# S7CAS-PLEIADES-CARTE-MERE_Pxx_DDR.net
KiCad netlist of a schematic drawn in Altium Designer
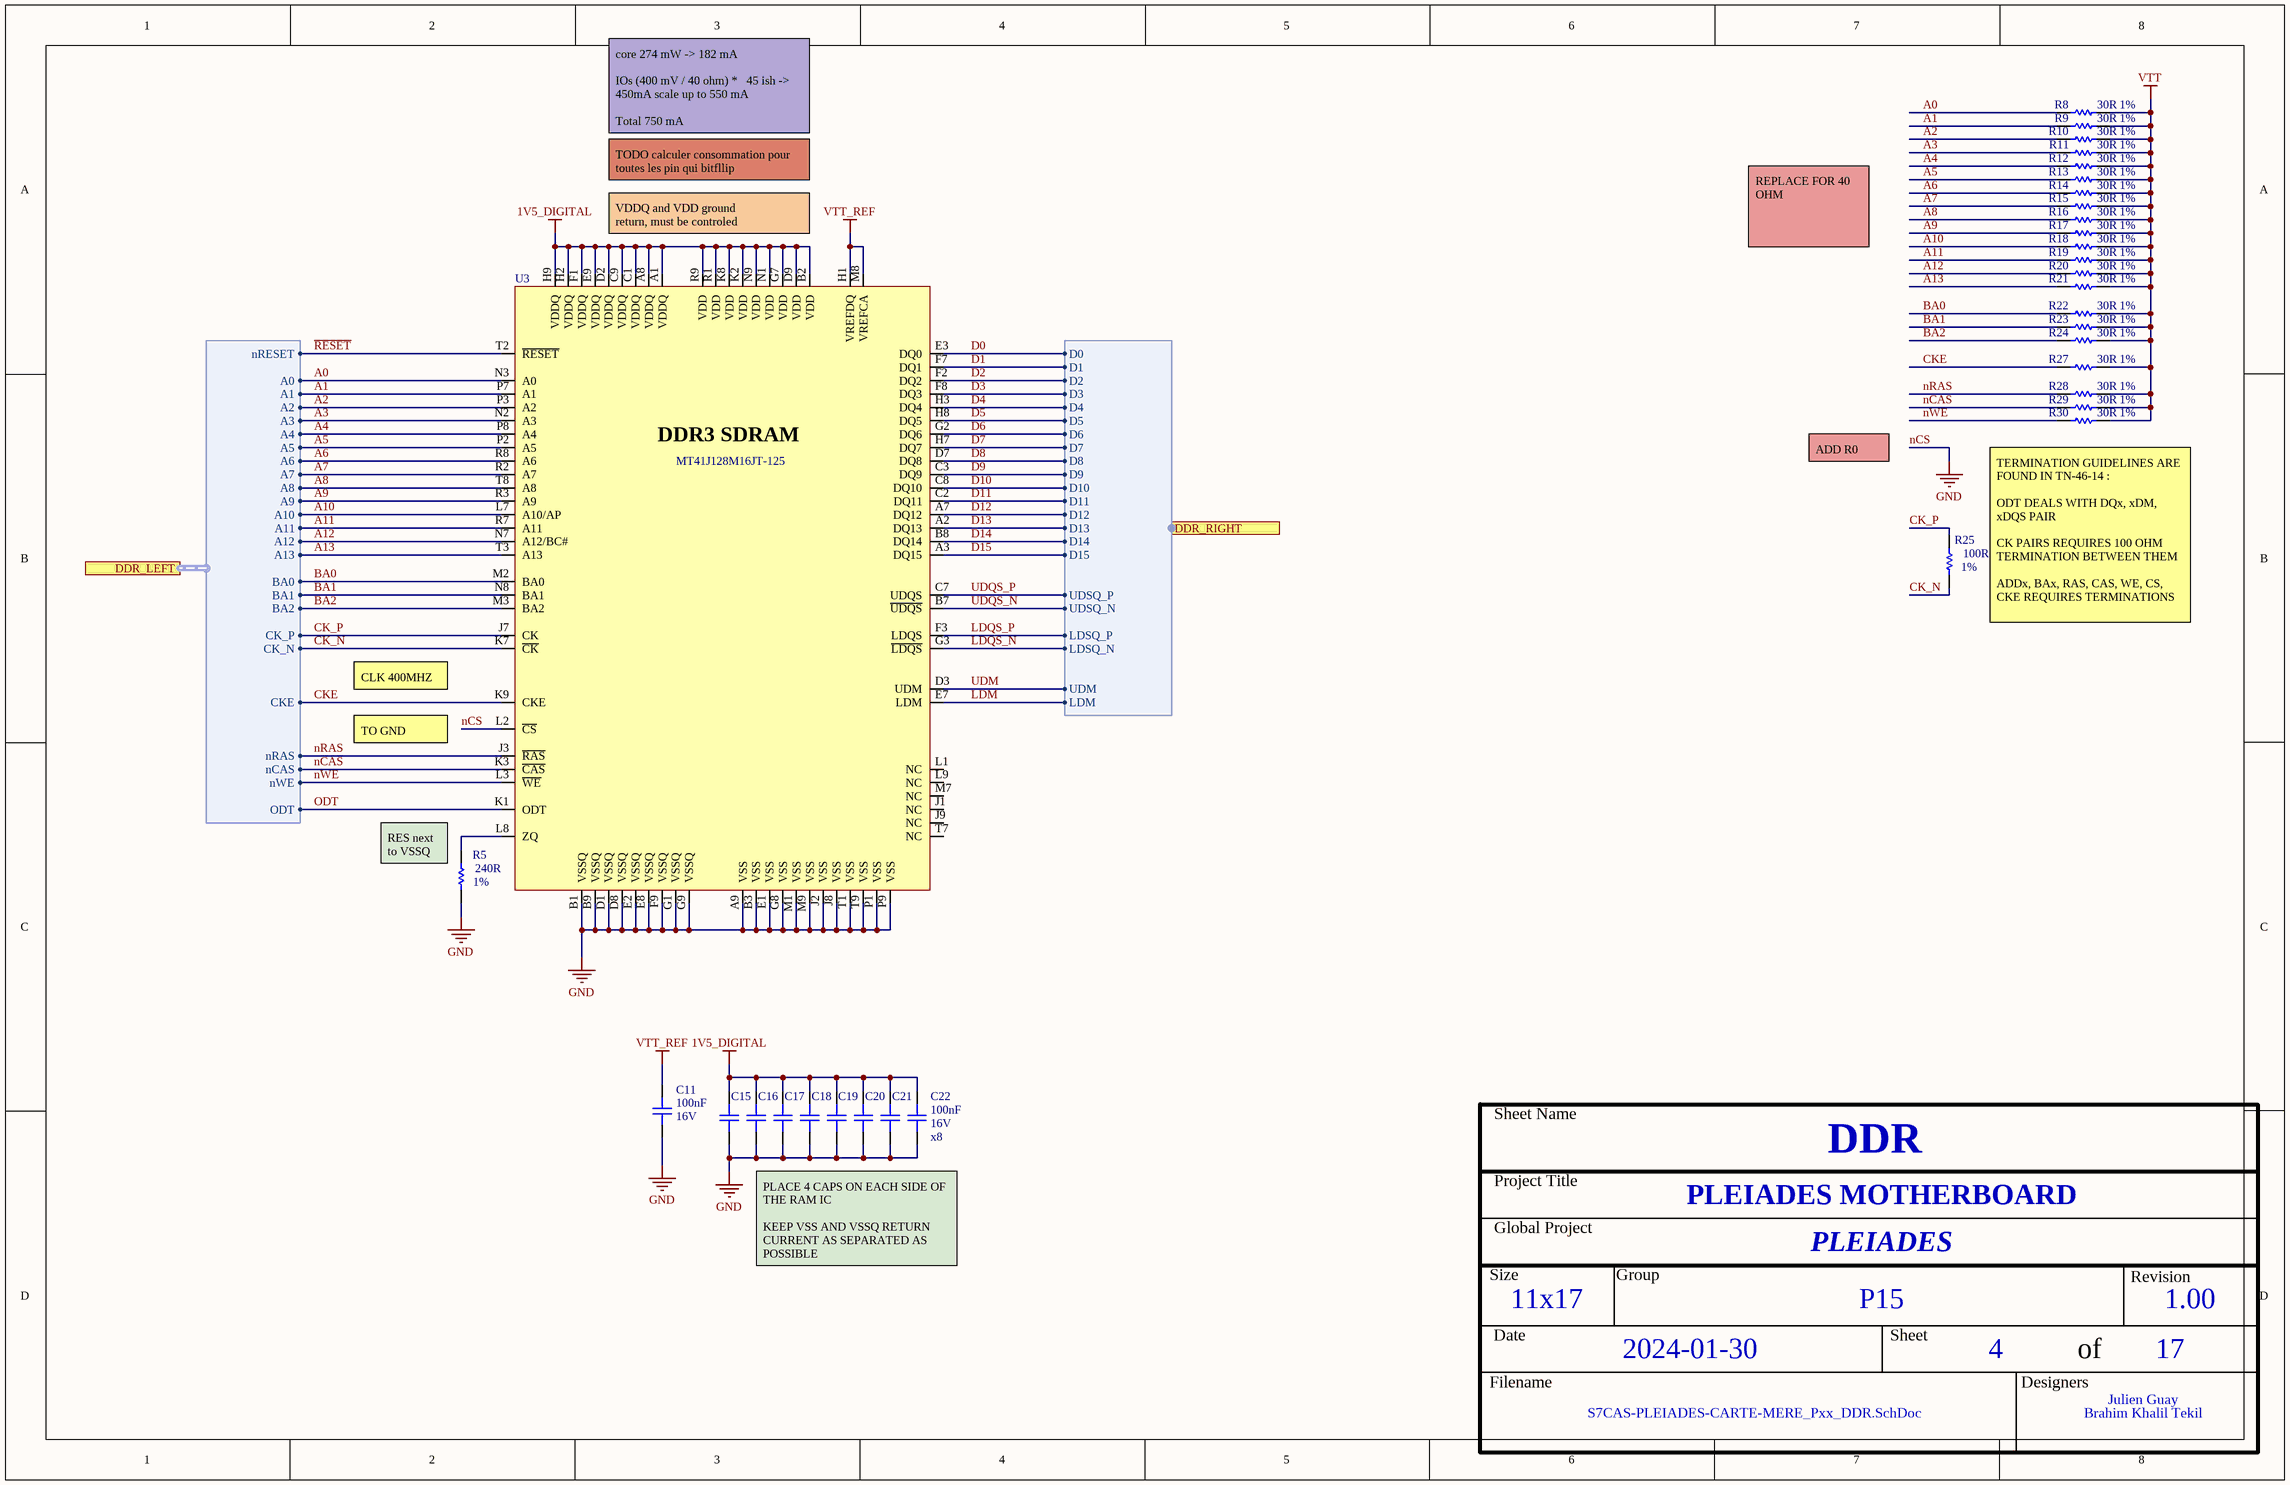
[diagram p0: S7CAS-PLEIADES-CARTE-MERE_Pxx_DDR.SchDoc]

(export (version "E")
  (design (tool "Eeschema 10.0.6"))
  (components
    (comp (ref "C11")
      (value "100nF")
      (footprint "CAP_0603")
      (description "CAP - 0603")
      (fields (field (name "VOLTAGE") "16V") (field (name "CREATEDBY") "Jonathan Bouchard"))
      (libsource (lib "S7CAS_LIB2023") (part "CAP - 0603"))
    )
    (comp (ref "C15")
      (value "CAP - 0603")
      (footprint "CAP_0603")
      (fields (field (name "VOLTAGE") "16V") (field (name "CREATEDBY") "Jonathan Bouchard"))
      (libsource (lib "S7CAS_LIB2023") (part "CAP - 0603"))
    )
    (comp (ref "C16")
      (value "CAP - 0603")
      (footprint "CAP_0603")
      (fields (field (name "VOLTAGE") "16V") (field (name "CREATEDBY") "Jonathan Bouchard"))
      (libsource (lib "S7CAS_LIB2023") (part "CAP - 0603"))
    )
    (comp (ref "C17")
      (value "CAP - 0603")
      (footprint "CAP_0603")
      (fields (field (name "VOLTAGE") "16V") (field (name "CREATEDBY") "Jonathan Bouchard"))
      (libsource (lib "S7CAS_LIB2023") (part "CAP - 0603"))
    )
    (comp (ref "C18")
      (value "CAP - 0603")
      (footprint "CAP_0603")
      (fields (field (name "VOLTAGE") "16V") (field (name "CREATEDBY") "Jonathan Bouchard"))
      (libsource (lib "S7CAS_LIB2023") (part "CAP - 0603"))
    )
    (comp (ref "C19")
      (value "CAP - 0603")
      (footprint "CAP_0603")
      (fields (field (name "VOLTAGE") "16V") (field (name "CREATEDBY") "Jonathan Bouchard"))
      (libsource (lib "S7CAS_LIB2023") (part "CAP - 0603"))
    )
    (comp (ref "C20")
      (value "CAP - 0603")
      (footprint "CAP_0603")
      (fields (field (name "VOLTAGE") "16V") (field (name "CREATEDBY") "Jonathan Bouchard"))
      (libsource (lib "S7CAS_LIB2023") (part "CAP - 0603"))
    )
    (comp (ref "C21")
      (value "CAP - 0603")
      (footprint "CAP_0603")
      (fields (field (name "VOLTAGE") "16V") (field (name "CREATEDBY") "Jonathan Bouchard"))
      (libsource (lib "S7CAS_LIB2023") (part "CAP - 0603"))
    )
    (comp (ref "C22")
      (value "100nF")
      (footprint "CAP_0603")
      (description "CAP - 0603")
      (fields (field (name "VOLTAGE") "16V") (field (name "CREATEDBY") "Jonathan Bouchard"))
      (libsource (lib "S7CAS_LIB2023") (part "CAP - 0603"))
    )
    (comp (ref "R5")
      (value "240R")
      (footprint "RES_0603")
      (description "RES - 0603")
      (fields (field (name "PRECISION") "1%") (field (name "CREATEDBY") "Jonathan Bouchard"))
      (libsource (lib "S7CAS_LIB2023") (part "RES - 0603"))
    )
    (comp (ref "R8")
      (value "30R")
      (footprint "RES_0603")
      (description "RES - 0603")
      (fields (field (name "PRECISION") "1%") (field (name "CREATEDBY") "Jonathan Bouchard"))
      (libsource (lib "S7CAS_LIB2023") (part "RES - 0603"))
    )
    (comp (ref "R9")
      (value "30R")
      (footprint "RES_0603")
      (description "RES - 0603")
      (fields (field (name "PRECISION") "1%") (field (name "CREATEDBY") "Jonathan Bouchard"))
      (libsource (lib "S7CAS_LIB2023") (part "RES - 0603"))
    )
    (comp (ref "R10")
      (value "30R")
      (footprint "RES_0603")
      (description "RES - 0603")
      (fields (field (name "PRECISION") "1%") (field (name "CREATEDBY") "Jonathan Bouchard"))
      (libsource (lib "S7CAS_LIB2023") (part "RES - 0603"))
    )
    (comp (ref "R11")
      (value "30R")
      (footprint "RES_0603")
      (description "RES - 0603")
      (fields (field (name "PRECISION") "1%") (field (name "CREATEDBY") "Jonathan Bouchard"))
      (libsource (lib "S7CAS_LIB2023") (part "RES - 0603"))
    )
    (comp (ref "R12")
      (value "30R")
      (footprint "RES_0603")
      (description "RES - 0603")
      (fields (field (name "PRECISION") "1%") (field (name "CREATEDBY") "Jonathan Bouchard"))
      (libsource (lib "S7CAS_LIB2023") (part "RES - 0603"))
    )
    (comp (ref "R13")
      (value "30R")
      (footprint "RES_0603")
      (description "RES - 0603")
      (fields (field (name "PRECISION") "1%") (field (name "CREATEDBY") "Jonathan Bouchard"))
      (libsource (lib "S7CAS_LIB2023") (part "RES - 0603"))
    )
    (comp (ref "R14")
      (value "30R")
      (footprint "RES_0603")
      (description "RES - 0603")
      (fields (field (name "PRECISION") "1%") (field (name "CREATEDBY") "Jonathan Bouchard"))
      (libsource (lib "S7CAS_LIB2023") (part "RES - 0603"))
    )
    (comp (ref "R15")
      (value "30R")
      (footprint "RES_0603")
      (description "RES - 0603")
      (fields (field (name "PRECISION") "1%") (field (name "CREATEDBY") "Jonathan Bouchard"))
      (libsource (lib "S7CAS_LIB2023") (part "RES - 0603"))
    )
    (comp (ref "R16")
      (value "30R")
      (footprint "RES_0603")
      (description "RES - 0603")
      (fields (field (name "PRECISION") "1%") (field (name "CREATEDBY") "Jonathan Bouchard"))
      (libsource (lib "S7CAS_LIB2023") (part "RES - 0603"))
    )
    (comp (ref "R17")
      (value "30R")
      (footprint "RES_0603")
      (description "RES - 0603")
      (fields (field (name "PRECISION") "1%") (field (name "CREATEDBY") "Jonathan Bouchard"))
      (libsource (lib "S7CAS_LIB2023") (part "RES - 0603"))
    )
    (comp (ref "R18")
      (value "30R")
      (footprint "RES_0603")
      (description "RES - 0603")
      (fields (field (name "PRECISION") "1%") (field (name "CREATEDBY") "Jonathan Bouchard"))
      (libsource (lib "S7CAS_LIB2023") (part "RES - 0603"))
    )
    (comp (ref "R19")
      (value "30R")
      (footprint "RES_0603")
      (description "RES - 0603")
      (fields (field (name "PRECISION") "1%") (field (name "CREATEDBY") "Jonathan Bouchard"))
      (libsource (lib "S7CAS_LIB2023") (part "RES - 0603"))
    )
    (comp (ref "R20")
      (value "30R")
      (footprint "RES_0603")
      (description "RES - 0603")
      (fields (field (name "PRECISION") "1%") (field (name "CREATEDBY") "Jonathan Bouchard"))
      (libsource (lib "S7CAS_LIB2023") (part "RES - 0603"))
    )
    (comp (ref "R21")
      (value "30R")
      (footprint "RES_0603")
      (description "RES - 0603")
      (fields (field (name "PRECISION") "1%") (field (name "CREATEDBY") "Jonathan Bouchard"))
      (libsource (lib "S7CAS_LIB2023") (part "RES - 0603"))
    )
    (comp (ref "R22")
      (value "30R")
      (footprint "RES_0603")
      (description "RES - 0603")
      (fields (field (name "PRECISION") "1%") (field (name "CREATEDBY") "Jonathan Bouchard"))
      (libsource (lib "S7CAS_LIB2023") (part "RES - 0603"))
    )
    (comp (ref "R23")
      (value "30R")
      (footprint "RES_0603")
      (description "RES - 0603")
      (fields (field (name "PRECISION") "1%") (field (name "CREATEDBY") "Jonathan Bouchard"))
      (libsource (lib "S7CAS_LIB2023") (part "RES - 0603"))
    )
    (comp (ref "R24")
      (value "30R")
      (footprint "RES_0603")
      (description "RES - 0603")
      (fields (field (name "PRECISION") "1%") (field (name "CREATEDBY") "Jonathan Bouchard"))
      (libsource (lib "S7CAS_LIB2023") (part "RES - 0603"))
    )
    (comp (ref "R25")
      (value "100R")
      (footprint "RES_0603")
      (description "RES - 0603")
      (fields (field (name "PRECISION") "1%") (field (name "CREATEDBY") "Jonathan Bouchard"))
      (libsource (lib "S7CAS_LIB2023") (part "RES - 0603"))
    )
    (comp (ref "R27")
      (value "30R")
      (footprint "RES_0603")
      (description "RES - 0603")
      (fields (field (name "PRECISION") "1%") (field (name "CREATEDBY") "Jonathan Bouchard"))
      (libsource (lib "S7CAS_LIB2023") (part "RES - 0603"))
    )
    (comp (ref "R28")
      (value "30R")
      (footprint "RES_0603")
      (description "RES - 0603")
      (fields (field (name "PRECISION") "1%") (field (name "CREATEDBY") "Jonathan Bouchard"))
      (libsource (lib "S7CAS_LIB2023") (part "RES - 0603"))
    )
    (comp (ref "R29")
      (value "30R")
      (footprint "RES_0603")
      (description "RES - 0603")
      (fields (field (name "PRECISION") "1%") (field (name "CREATEDBY") "Jonathan Bouchard"))
      (libsource (lib "S7CAS_LIB2023") (part "RES - 0603"))
    )
    (comp (ref "R30")
      (value "30R")
      (footprint "RES_0603")
      (description "RES - 0603")
      (fields (field (name "PRECISION") "1%") (field (name "CREATEDBY") "Jonathan Bouchard"))
      (libsource (lib "S7CAS_LIB2023") (part "RES - 0603"))
    )
    (comp (ref "U3")
      (value "MT41J128M16JT-125")
      (footprint "MEM_DDR3_MT41J128M16JT-125")
      (description "MEM - DDR3 SDRAM 2GBIT 800MHZ - TFBGA-96")
      (fields
        (field (name "VOLTAGE") "1.425 V ~ 1.575 V")
        (field (name "MFG") "Micrel")
        (field (name "CREATEDBY") "Jonathan Bouchard")
      )
      (libsource (lib "S7CAS_LIB2023") (part "MEM_DDR3_MT41J128M16JT-125{colon}K TR"))
    )
  )
  (nets
    (net (code "3") (name "/A0") (class "Default")
      (node (ref "R8") (pin "2") (pinfunction "2_2") (pintype "passive"))
      (node (ref "U3") (pin "N3") (pinfunction "A0_N3") (pintype "passive"))
    )
    (net (code "4") (name "/A1") (class "Default")
      (node (ref "R9") (pin "2") (pinfunction "2_2") (pintype "passive"))
      (node (ref "U3") (pin "P7") (pinfunction "A1_P7") (pintype "passive"))
    )
    (net (code "5") (name "/A2") (class "Default")
      (node (ref "R10") (pin "2") (pinfunction "2_2") (pintype "passive"))
      (node (ref "U3") (pin "P3") (pinfunction "A2_P3") (pintype "passive"))
    )
    (net (code "6") (name "/A3") (class "Default")
      (node (ref "R11") (pin "2") (pinfunction "2_2") (pintype "passive"))
      (node (ref "U3") (pin "N2") (pinfunction "A3_N2") (pintype "passive"))
    )
    (net (code "7") (name "/A4") (class "Default")
      (node (ref "R12") (pin "2") (pinfunction "2_2") (pintype "passive"))
      (node (ref "U3") (pin "P8") (pinfunction "A4_P8") (pintype "passive"))
    )
    (net (code "8") (name "/A5") (class "Default")
      (node (ref "R13") (pin "2") (pinfunction "2_2") (pintype "passive"))
      (node (ref "U3") (pin "P2") (pinfunction "A5_P2") (pintype "passive"))
    )
    (net (code "9") (name "/A6") (class "Default")
      (node (ref "R14") (pin "2") (pinfunction "2_2") (pintype "passive"))
      (node (ref "U3") (pin "R8") (pinfunction "A6_R8") (pintype "passive"))
    )
    (net (code "10") (name "/A7") (class "Default")
      (node (ref "R15") (pin "2") (pinfunction "2_2") (pintype "passive"))
      (node (ref "U3") (pin "R2") (pinfunction "A7_R2") (pintype "passive"))
    )
    (net (code "11") (name "/A8") (class "Default")
      (node (ref "R16") (pin "2") (pinfunction "2_2") (pintype "passive"))
      (node (ref "U3") (pin "T8") (pinfunction "A8_T8") (pintype "passive"))
    )
    (net (code "12") (name "/A9") (class "Default")
      (node (ref "R17") (pin "2") (pinfunction "2_2") (pintype "passive"))
      (node (ref "U3") (pin "R3") (pinfunction "A9_R3") (pintype "passive"))
    )
    (net (code "13") (name "/A10") (class "Default")
      (node (ref "R18") (pin "2") (pinfunction "2_2") (pintype "passive"))
      (node (ref "U3") (pin "L7") (pinfunction "A10/AP_L7") (pintype "passive"))
    )
    (net (code "14") (name "/A11") (class "Default")
      (node (ref "R19") (pin "2") (pinfunction "2_2") (pintype "passive"))
      (node (ref "U3") (pin "R7") (pinfunction "A11_R7") (pintype "passive"))
    )
    (net (code "15") (name "/A12") (class "Default")
      (node (ref "R20") (pin "2") (pinfunction "2_2") (pintype "passive"))
      (node (ref "U3") (pin "N7") (pinfunction "A12/BC#_N7") (pintype "passive"))
    )
    (net (code "16") (name "/A13") (class "Default")
      (node (ref "R21") (pin "2") (pinfunction "2_2") (pintype "passive"))
      (node (ref "U3") (pin "T3") (pinfunction "A13_T3") (pintype "passive"))
    )
    (net (code "17") (name "/BA0") (class "Default")
      (node (ref "R22") (pin "2") (pinfunction "2_2") (pintype "passive"))
      (node (ref "U3") (pin "M2") (pinfunction "BA0_M2") (pintype "passive"))
    )
    (net (code "18") (name "/BA1") (class "Default")
      (node (ref "R23") (pin "2") (pinfunction "2_2") (pintype "passive"))
      (node (ref "U3") (pin "N8") (pinfunction "BA1_N8") (pintype "passive"))
    )
    (net (code "19") (name "/BA2") (class "Default")
      (node (ref "R24") (pin "2") (pinfunction "2_2") (pintype "passive"))
      (node (ref "U3") (pin "M3") (pinfunction "BA2_M3") (pintype "passive"))
    )
    (net (code "20") (name "/CKE") (class "Default")
      (node (ref "R27") (pin "2") (pinfunction "2_2") (pintype "passive"))
      (node (ref "U3") (pin "K9") (pinfunction "CKE_K9") (pintype "passive"))
    )
    (net (code "21") (name "/CK_N") (class "Default")
      (node (ref "R25") (pin "1") (pinfunction "1_1") (pintype "passive"))
      (node (ref "U3") (pin "K7") (pinfunction "CK_K7") (pintype "passive"))
    )
    (net (code "22") (name "/CK_P") (class "Default")
      (node (ref "R25") (pin "2") (pinfunction "2_2") (pintype "passive"))
      (node (ref "U3") (pin "J7") (pinfunction "CK_J7") (pintype "passive"))
    )
    (net (code "23") (name "/D0") (class "Default")
      (node (ref "U3") (pin "E3") (pinfunction "DQ0_E3") (pintype "passive"))
    )
    (net (code "24") (name "/D1") (class "Default")
      (node (ref "U3") (pin "F7") (pinfunction "DQ1_F7") (pintype "passive"))
    )
    (net (code "25") (name "/D2") (class "Default")
      (node (ref "U3") (pin "F2") (pinfunction "DQ2_F2") (pintype "passive"))
    )
    (net (code "26") (name "/D3") (class "Default")
      (node (ref "U3") (pin "F8") (pinfunction "DQ3_F8") (pintype "passive"))
    )
    (net (code "27") (name "/D4") (class "Default")
      (node (ref "U3") (pin "H3") (pinfunction "DQ4_H3") (pintype "passive"))
    )
    (net (code "28") (name "/D5") (class "Default")
      (node (ref "U3") (pin "H8") (pinfunction "DQ5_H8") (pintype "passive"))
    )
    (net (code "29") (name "/D6") (class "Default")
      (node (ref "U3") (pin "G2") (pinfunction "DQ6_G2") (pintype "passive"))
    )
    (net (code "30") (name "/D7") (class "Default")
      (node (ref "U3") (pin "H7") (pinfunction "DQ7_H7") (pintype "passive"))
    )
    (net (code "31") (name "/D8") (class "Default")
      (node (ref "U3") (pin "D7") (pinfunction "DQ8_D7") (pintype "passive"))
    )
    (net (code "32") (name "/D9") (class "Default")
      (node (ref "U3") (pin "C3") (pinfunction "DQ9_C3") (pintype "passive"))
    )
    (net (code "33") (name "/D10") (class "Default")
      (node (ref "U3") (pin "C8") (pinfunction "DQ10_C8") (pintype "passive"))
    )
    (net (code "34") (name "/D11") (class "Default")
      (node (ref "U3") (pin "C2") (pinfunction "DQ11_C2") (pintype "passive"))
    )
    (net (code "35") (name "/D12") (class "Default")
      (node (ref "U3") (pin "A7") (pinfunction "DQ12_A7") (pintype "passive"))
    )
    (net (code "36") (name "/D13") (class "Default")
      (node (ref "U3") (pin "A2") (pinfunction "DQ13_A2") (pintype "passive"))
    )
    (net (code "37") (name "/D14") (class "Default")
      (node (ref "U3") (pin "B8") (pinfunction "DQ14_B8") (pintype "passive"))
    )
    (net (code "38") (name "/D15") (class "Default")
      (node (ref "U3") (pin "A3") (pinfunction "DQ15_A3") (pintype "passive"))
    )
    (net (code "39") (name "/LDM") (class "Default")
      (node (ref "U3") (pin "E7") (pinfunction "LDM_E7") (pintype "passive"))
    )
    (net (code "40") (name "/LDQS_N") (class "Default")
      (node (ref "U3") (pin "G3") (pinfunction "LDQS_G3") (pintype "passive"))
    )
    (net (code "41") (name "/LDQS_P") (class "Default")
      (node (ref "U3") (pin "F3") (pinfunction "LDQS_F3") (pintype "passive"))
    )
    (net (code "42") (name "/ODT") (class "Default")
      (node (ref "U3") (pin "K1") (pinfunction "ODT_K1") (pintype "passive"))
    )
    (net (code "43") (name "/RESET") (class "Default")
      (node (ref "U3") (pin "T2") (pinfunction "RESET_T2") (pintype "passive"))
    )
    (net (code "44") (name "/UDM") (class "Default")
      (node (ref "U3") (pin "D3") (pinfunction "UDM_D3") (pintype "passive"))
    )
    (net (code "45") (name "/UDQS_N") (class "Default")
      (node (ref "U3") (pin "B7") (pinfunction "UDQS_B7") (pintype "passive"))
    )
    (net (code "46") (name "/UDQS_P") (class "Default")
      (node (ref "U3") (pin "C7") (pinfunction "UDQS_C7") (pintype "passive"))
    )
    (net (code "47") (name "/nCAS") (class "Default")
      (node (ref "R29") (pin "2") (pinfunction "2_2") (pintype "passive"))
      (node (ref "U3") (pin "K3") (pinfunction "CAS_K3") (pintype "passive"))
    )
    (net (code "48") (name "/nRAS") (class "Default")
      (node (ref "R28") (pin "2") (pinfunction "2_2") (pintype "passive"))
      (node (ref "U3") (pin "J3") (pinfunction "RAS_J3") (pintype "passive"))
    )
    (net (code "49") (name "/nWE") (class "Default")
      (node (ref "R30") (pin "2") (pinfunction "2_2") (pintype "passive"))
      (node (ref "U3") (pin "L3") (pinfunction "WE_L3") (pintype "passive"))
    )
    (net (code "52") (name "1V5_DIGITAL") (class "Default")
      (node (ref "C15") (pin "2") (pinfunction "2_2") (pintype "passive"))
      (node (ref "C16") (pin "2") (pinfunction "2_2") (pintype "passive"))
      (node (ref "C17") (pin "2") (pinfunction "2_2") (pintype "passive"))
      (node (ref "C18") (pin "2") (pinfunction "2_2") (pintype "passive"))
      (node (ref "C19") (pin "2") (pinfunction "2_2") (pintype "passive"))
      (node (ref "C20") (pin "2") (pinfunction "2_2") (pintype "passive"))
      (node (ref "C21") (pin "2") (pinfunction "2_2") (pintype "passive"))
      (node (ref "C22") (pin "2") (pinfunction "2_2") (pintype "passive"))
      (node (ref "U3") (pin "A1") (pinfunction "VDDQ_A1") (pintype "passive"))
      (node (ref "U3") (pin "A8") (pinfunction "VDDQ_A8") (pintype "passive"))
      (node (ref "U3") (pin "B2") (pinfunction "VDD_B2") (pintype "passive"))
      (node (ref "U3") (pin "C1") (pinfunction "VDDQ_C1") (pintype "passive"))
      (node (ref "U3") (pin "C9") (pinfunction "VDDQ_C9") (pintype "passive"))
      (node (ref "U3") (pin "D2") (pinfunction "VDDQ_D2") (pintype "passive"))
      (node (ref "U3") (pin "D9") (pinfunction "VDD_D9") (pintype "passive"))
      (node (ref "U3") (pin "E9") (pinfunction "VDDQ_E9") (pintype "passive"))
      (node (ref "U3") (pin "F1") (pinfunction "VDDQ_F1") (pintype "passive"))
      (node (ref "U3") (pin "G7") (pinfunction "VDD_G7") (pintype "passive"))
      (node (ref "U3") (pin "H2") (pinfunction "VDDQ_H2") (pintype "passive"))
      (node (ref "U3") (pin "H9") (pinfunction "VDDQ_H9") (pintype "passive"))
      (node (ref "U3") (pin "K2") (pinfunction "VDD_K2") (pintype "passive"))
      (node (ref "U3") (pin "K8") (pinfunction "VDD_K8") (pintype "passive"))
      (node (ref "U3") (pin "N1") (pinfunction "VDD_N1") (pintype "passive"))
      (node (ref "U3") (pin "N9") (pinfunction "VDD_N9") (pintype "passive"))
      (node (ref "U3") (pin "R1") (pinfunction "VDD_R1") (pintype "passive"))
      (node (ref "U3") (pin "R9") (pinfunction "VDD_R9") (pintype "passive"))
    )
    (net (code "53") (name "GND") (class "Default")
      (node (ref "C11") (pin "1") (pinfunction "1_1") (pintype "passive"))
      (node (ref "C15") (pin "1") (pinfunction "1_1") (pintype "passive"))
      (node (ref "C16") (pin "1") (pinfunction "1_1") (pintype "passive"))
      (node (ref "C17") (pin "1") (pinfunction "1_1") (pintype "passive"))
      (node (ref "C18") (pin "1") (pinfunction "1_1") (pintype "passive"))
      (node (ref "C19") (pin "1") (pinfunction "1_1") (pintype "passive"))
      (node (ref "C20") (pin "1") (pinfunction "1_1") (pintype "passive"))
      (node (ref "C21") (pin "1") (pinfunction "1_1") (pintype "passive"))
      (node (ref "C22") (pin "1") (pinfunction "1_1") (pintype "passive"))
      (node (ref "R5") (pin "1") (pinfunction "1_1") (pintype "passive"))
      (node (ref "U3") (pin "A9") (pinfunction "VSS_A9") (pintype "passive"))
      (node (ref "U3") (pin "B1") (pinfunction "VSSQ_B1") (pintype "passive"))
      (node (ref "U3") (pin "B3") (pinfunction "VSS_B3") (pintype "passive"))
      (node (ref "U3") (pin "B9") (pinfunction "VSSQ_B9") (pintype "passive"))
      (node (ref "U3") (pin "D1") (pinfunction "VSSQ_D1") (pintype "passive"))
      (node (ref "U3") (pin "D8") (pinfunction "VSSQ_D8") (pintype "passive"))
      (node (ref "U3") (pin "E1") (pinfunction "VSS_E1") (pintype "passive"))
      (node (ref "U3") (pin "E2") (pinfunction "VSSQ_E2") (pintype "passive"))
      (node (ref "U3") (pin "E8") (pinfunction "VSSQ_E8") (pintype "passive"))
      (node (ref "U3") (pin "F9") (pinfunction "VSSQ_F9") (pintype "passive"))
      (node (ref "U3") (pin "G1") (pinfunction "VSSQ_G1") (pintype "passive"))
      (node (ref "U3") (pin "G8") (pinfunction "VSS_G8") (pintype "passive"))
      (node (ref "U3") (pin "G9") (pinfunction "VSSQ_G9") (pintype "passive"))
      (node (ref "U3") (pin "J2") (pinfunction "VSS_J2") (pintype "passive"))
      (node (ref "U3") (pin "J8") (pinfunction "VSS_J8") (pintype "passive"))
      (node (ref "U3") (pin "L2") (pinfunction "CS_L2") (pintype "passive"))
      (node (ref "U3") (pin "M1") (pinfunction "VSS_M1") (pintype "passive"))
      (node (ref "U3") (pin "M9") (pinfunction "VSS_M9") (pintype "passive"))
      (node (ref "U3") (pin "P1") (pinfunction "VSS_P1") (pintype "passive"))
      (node (ref "U3") (pin "P9") (pinfunction "VSS_P9") (pintype "passive"))
      (node (ref "U3") (pin "T1") (pinfunction "VSS_T1") (pintype "passive"))
      (node (ref "U3") (pin "T9") (pinfunction "VSS_T9") (pintype "passive"))
    )
    (net (code "54") (name "Net-(U3-ZQ)") (class "Default")
      (node (ref "R5") (pin "2") (pinfunction "2_2") (pintype "passive"))
      (node (ref "U3") (pin "L8") (pinfunction "ZQ_L8") (pintype "passive"))
    )
    (net (code "55") (name "VTT") (class "Default")
      (node (ref "R10") (pin "1") (pinfunction "1_1") (pintype "passive"))
      (node (ref "R11") (pin "1") (pinfunction "1_1") (pintype "passive"))
      (node (ref "R12") (pin "1") (pinfunction "1_1") (pintype "passive"))
      (node (ref "R13") (pin "1") (pinfunction "1_1") (pintype "passive"))
      (node (ref "R14") (pin "1") (pinfunction "1_1") (pintype "passive"))
      (node (ref "R15") (pin "1") (pinfunction "1_1") (pintype "passive"))
      (node (ref "R16") (pin "1") (pinfunction "1_1") (pintype "passive"))
      (node (ref "R17") (pin "1") (pinfunction "1_1") (pintype "passive"))
      (node (ref "R18") (pin "1") (pinfunction "1_1") (pintype "passive"))
      (node (ref "R19") (pin "1") (pinfunction "1_1") (pintype "passive"))
      (node (ref "R20") (pin "1") (pinfunction "1_1") (pintype "passive"))
      (node (ref "R21") (pin "1") (pinfunction "1_1") (pintype "passive"))
      (node (ref "R22") (pin "1") (pinfunction "1_1") (pintype "passive"))
      (node (ref "R23") (pin "1") (pinfunction "1_1") (pintype "passive"))
      (node (ref "R24") (pin "1") (pinfunction "1_1") (pintype "passive"))
      (node (ref "R27") (pin "1") (pinfunction "1_1") (pintype "passive"))
      (node (ref "R28") (pin "1") (pinfunction "1_1") (pintype "passive"))
      (node (ref "R29") (pin "1") (pinfunction "1_1") (pintype "passive"))
      (node (ref "R30") (pin "1") (pinfunction "1_1") (pintype "passive"))
      (node (ref "R8") (pin "1") (pinfunction "1_1") (pintype "passive"))
      (node (ref "R9") (pin "1") (pinfunction "1_1") (pintype "passive"))
    )
    (net (code "56") (name "VTT_REF") (class "Default")
      (node (ref "C11") (pin "2") (pinfunction "2_2") (pintype "passive"))
      (node (ref "U3") (pin "H1") (pinfunction "VREFDQ_H1") (pintype "passive"))
      (node (ref "U3") (pin "M8") (pinfunction "VREFCA_M8") (pintype "passive"))
    )
    (net (code "57") (name "unconnected-(U3-NC-PadJ1)") (class "Default")
      (node (ref "U3") (pin "J1") (pinfunction "NC_J1") (pintype "passive"))
    )
    (net (code "58") (name "unconnected-(U3-NC-PadJ9)") (class "Default")
      (node (ref "U3") (pin "J9") (pinfunction "NC_J9") (pintype "passive"))
    )
    (net (code "59") (name "unconnected-(U3-NC-PadL1)") (class "Default")
      (node (ref "U3") (pin "L1") (pinfunction "NC_L1") (pintype "passive"))
    )
    (net (code "60") (name "unconnected-(U3-NC-PadL9)") (class "Default")
      (node (ref "U3") (pin "L9") (pinfunction "NC_L9") (pintype "passive"))
    )
    (net (code "61") (name "unconnected-(U3-NC-PadM7)") (class "Default")
      (node (ref "U3") (pin "M7") (pinfunction "NC_M7") (pintype "passive"))
    )
    (net (code "62") (name "unconnected-(U3-NC-PadT7)") (class "Default")
      (node (ref "U3") (pin "T7") (pinfunction "NC_T7") (pintype "passive"))
    )
  )
)
